# 4digitSSD-MAX7219CNG.net
KiCad netlist of a schematic drawn in EAGLE
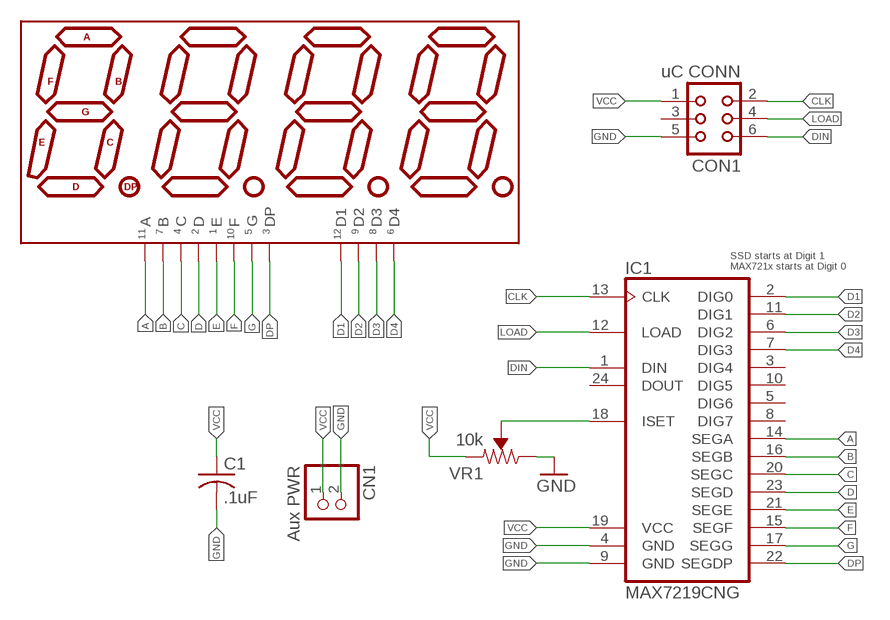
[diagram p0: schematic, sheet 1]

(export (version "E")
  (design (tool "Eeschema 10.0.6"))
  (components
    (comp (ref "C1")
      (value ".1uF")
      (footprint "eagle-import:C1206")
      (libsource (lib "eagle-import") (part "C-USC1206"))
    )
    (comp (ref "CN1")
      (value "Aux PWR")
      (footprint "eagle-import:JST-PH-2-THM")
      (libsource (lib "eagle-import") (part "JST_2PIN-THM"))
    )
    (comp (ref "CON1")
      (value "uC CONN")
      (footprint "eagle-import:CON06")
      (libsource (lib "eagle-import") (part "CON06"))
    )
    (comp (ref "IC1")
      (value "MAX7219CNG")
      (footprint "eagle-import:DIL24-3")
      (fields (field (name "MF") "MAXIM"))
      (libsource (lib "eagle-import") (part "MAX7219CNG"))
    )
    (comp (ref "U$1")
      (value "7-SEGMENT-4DIGIT-COUNTERPTH")
      (footprint "eagle-import:7-SEGMENT-4DIGIT-COUNTER")
      (libsource (lib "eagle-import") (part "7-SEGMENT-4DIGIT-COUNTERPTH"))
    )
    (comp (ref "VR1")
      (value "10k")
      (footprint "eagle-import:TRIMPOT-PTH-3386U")
      (libsource (lib "eagle-import") (part "TRIMPOT-PTH-10MM-KNOB-1/2W-10%"))
    )
  )
  (nets
    (net (code "1") (name "A") (class "Default")
      (node (ref "IC1") (pin "14") (pinfunction "SEGA_14") (pintype "output"))
      (node (ref "U$1") (pin "11") (pinfunction "A_11") (pintype "bidirectional"))
    )
    (net (code "2") (name "B") (class "Default")
      (node (ref "IC1") (pin "16") (pinfunction "SEGB_16") (pintype "output"))
      (node (ref "U$1") (pin "7") (pinfunction "B_7") (pintype "bidirectional"))
    )
    (net (code "3") (name "C") (class "Default")
      (node (ref "IC1") (pin "20") (pinfunction "SEGC_20") (pintype "output"))
      (node (ref "U$1") (pin "4") (pinfunction "C_4") (pintype "bidirectional"))
    )
    (net (code "4") (name "CLK") (class "Default")
      (node (ref "CON1") (pin "2") (pinfunction "2_2") (pintype "passive"))
      (node (ref "IC1") (pin "13") (pinfunction "CLK_13") (pintype "input"))
    )
    (net (code "5") (name "D") (class "Default")
      (node (ref "IC1") (pin "23") (pinfunction "SEGD_23") (pintype "output"))
      (node (ref "U$1") (pin "2") (pinfunction "D_2") (pintype "bidirectional"))
    )
    (net (code "6") (name "D1") (class "Default")
      (node (ref "IC1") (pin "2") (pinfunction "DIG0_2") (pintype "output"))
      (node (ref "U$1") (pin "12") (pinfunction "D1_12") (pintype "bidirectional"))
    )
    (net (code "7") (name "D2") (class "Default")
      (node (ref "IC1") (pin "11") (pinfunction "DIG1_11") (pintype "output"))
      (node (ref "U$1") (pin "9") (pinfunction "D2_9") (pintype "bidirectional"))
    )
    (net (code "8") (name "D3") (class "Default")
      (node (ref "IC1") (pin "6") (pinfunction "DIG2_6") (pintype "output"))
      (node (ref "U$1") (pin "8") (pinfunction "D3_8") (pintype "bidirectional"))
    )
    (net (code "9") (name "D4") (class "Default")
      (node (ref "IC1") (pin "7") (pinfunction "DIG3_7") (pintype "output"))
      (node (ref "U$1") (pin "6") (pinfunction "D4_6") (pintype "bidirectional"))
    )
    (net (code "10") (name "DIN") (class "Default")
      (node (ref "CON1") (pin "6") (pinfunction "6_6") (pintype "passive"))
      (node (ref "IC1") (pin "1") (pinfunction "DIN_1") (pintype "input"))
    )
    (net (code "11") (name "DP") (class "Default")
      (node (ref "IC1") (pin "22") (pinfunction "SEGDP_22") (pintype "output"))
      (node (ref "U$1") (pin "3") (pinfunction "DP_3") (pintype "bidirectional"))
    )
    (net (code "12") (name "E") (class "Default")
      (node (ref "IC1") (pin "21") (pinfunction "SEGE_21") (pintype "output"))
      (node (ref "U$1") (pin "1") (pinfunction "E_1") (pintype "bidirectional"))
    )
    (net (code "13") (name "F") (class "Default")
      (node (ref "IC1") (pin "15") (pinfunction "SEGF_15") (pintype "output"))
      (node (ref "U$1") (pin "10") (pinfunction "F_10") (pintype "bidirectional"))
    )
    (net (code "14") (name "G") (class "Default")
      (node (ref "IC1") (pin "17") (pinfunction "SEGG_17") (pintype "output"))
      (node (ref "U$1") (pin "5") (pinfunction "G_5") (pintype "bidirectional"))
    )
    (net (code "15") (name "GND") (class "Default")
      (node (ref "C1") (pin "2") (pinfunction "2_2") (pintype "passive"))
      (node (ref "CN1") (pin "2") (pinfunction "1_2") (pintype "passive"))
      (node (ref "CON1") (pin "5") (pinfunction "5_5") (pintype "passive"))
      (node (ref "IC1") (pin "4") (pinfunction "GND_4") (pintype "power_in"))
      (node (ref "IC1") (pin "9") (pinfunction "GND_9") (pintype "power_in"))
      (node (ref "VR1") (pin "3") (pinfunction "CW_3") (pintype "passive"))
    )
    (net (code "16") (name "LOAD") (class "Default")
      (node (ref "CON1") (pin "4") (pinfunction "4_4") (pintype "passive"))
      (node (ref "IC1") (pin "12") (pinfunction "LOAD_12") (pintype "input"))
    )
    (net (code "17") (name "Net-(IC1-ISET)") (class "Default")
      (node (ref "IC1") (pin "18") (pinfunction "ISET_18") (pintype "input"))
      (node (ref "VR1") (pin "2") (pinfunction "WIPER_2") (pintype "passive"))
    )
    (net (code "18") (name "VCC") (class "Default")
      (node (ref "C1") (pin "1") (pinfunction "1_1") (pintype "passive"))
      (node (ref "CN1") (pin "1") (pinfunction "2_1") (pintype "passive"))
      (node (ref "CON1") (pin "1") (pinfunction "1_1") (pintype "passive"))
      (node (ref "IC1") (pin "19") (pinfunction "VCC_19") (pintype "power_in"))
      (node (ref "VR1") (pin "1") (pinfunction "CCW_1") (pintype "passive"))
    )
    (net (code "19") (name "unconnected-(CON1-Pad3)") (class "Default")
      (node (ref "CON1") (pin "3") (pinfunction "3_3") (pintype "passive"))
    )
    (net (code "20") (name "unconnected-(IC1-DIG4-Pad3)") (class "Default")
      (node (ref "IC1") (pin "3") (pinfunction "DIG4_3") (pintype "output"))
    )
    (net (code "21") (name "unconnected-(IC1-DIG5-Pad10)") (class "Default")
      (node (ref "IC1") (pin "10") (pinfunction "DIG5_10") (pintype "output"))
    )
    (net (code "22") (name "unconnected-(IC1-DIG6-Pad5)") (class "Default")
      (node (ref "IC1") (pin "5") (pinfunction "DIG6_5") (pintype "output"))
    )
    (net (code "23") (name "unconnected-(IC1-DIG7-Pad8)") (class "Default")
      (node (ref "IC1") (pin "8") (pinfunction "DIG7_8") (pintype "output"))
    )
    (net (code "24") (name "unconnected-(IC1-DOUT-Pad24)") (class "Default")
      (node (ref "IC1") (pin "24") (pinfunction "DOUT_24") (pintype "output"))
    )
  )
)
